# B2B_connectors.net
KiCad netlist of a schematic drawn in Altium Designer
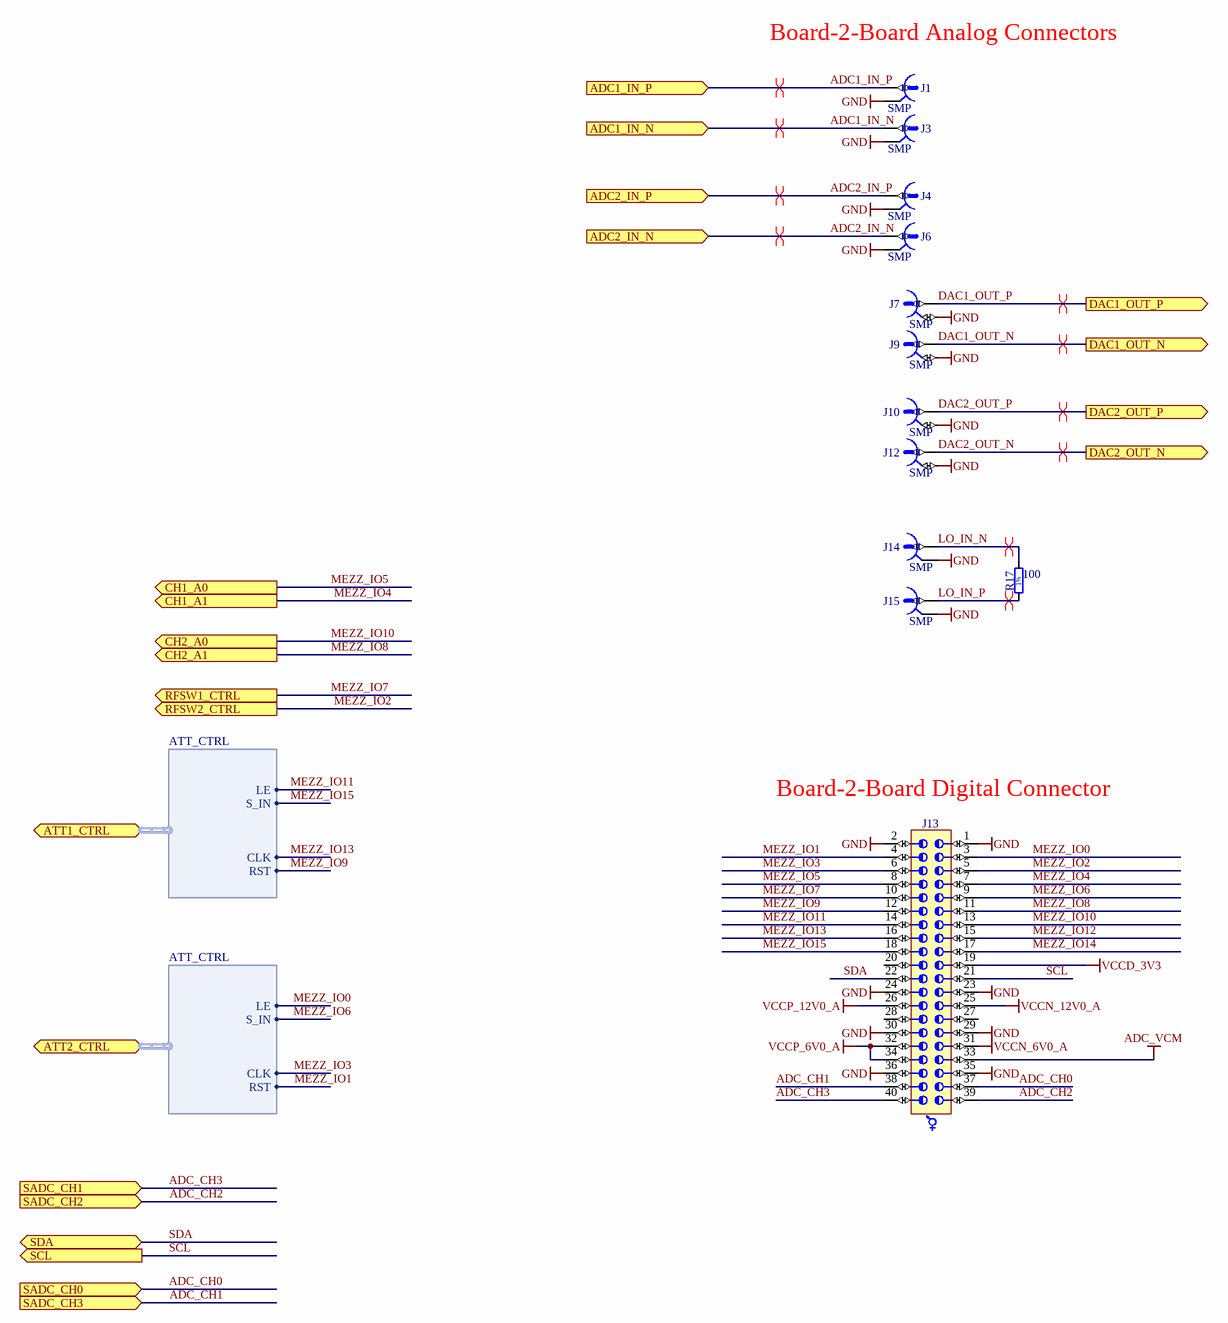
[diagram p0: B2B_connectors .SchDoc]

(export (version "E")
  (design (tool "Eeschema 10.0.6"))
  (components
    (comp (ref "J1")
      (value "SMP")
      (footprint "AMPHENOL_SMP-MSLD-PCT-10")
      (description "50 Ohms, SMP Surface/THT Mount Plug, Limited Detent")
      (fields
        (field (name "PART NUMBER") "AMPHENOL_SMP-MSLD-PCT-10")
        (field (name "MANUFACTURER") "AMPHENOL")
        (field (name "AUTHOR") "GK")
      )
      (libsource (lib "LIBRARY_SCH") (part "CON_SMP-MSLD-PCT-10"))
    )
    (comp (ref "J3")
      (value "SMP")
      (footprint "AMPHENOL_SMP-MSLD-PCT-10")
      (description "50 Ohms, SMP Surface/THT Mount Plug, Limited Detent")
      (fields
        (field (name "PART NUMBER") "AMPHENOL_SMP-MSLD-PCT-10")
        (field (name "MANUFACTURER") "AMPHENOL")
        (field (name "AUTHOR") "GK")
      )
      (libsource (lib "LIBRARY_SCH") (part "CON_SMP-MSLD-PCT-10"))
    )
    (comp (ref "J4")
      (value "SMP")
      (footprint "AMPHENOL_SMP-MSLD-PCT-10")
      (description "50 Ohms, SMP Surface/THT Mount Plug, Limited Detent")
      (fields
        (field (name "PART NUMBER") "AMPHENOL_SMP-MSLD-PCT-10")
        (field (name "MANUFACTURER") "AMPHENOL")
        (field (name "AUTHOR") "GK")
      )
      (libsource (lib "LIBRARY_SCH") (part "CON_SMP-MSLD-PCT-10"))
    )
    (comp (ref "J6")
      (value "SMP")
      (footprint "AMPHENOL_SMP-MSLD-PCT-10")
      (description "50 Ohms, SMP Surface/THT Mount Plug, Limited Detent")
      (fields
        (field (name "PART NUMBER") "AMPHENOL_SMP-MSLD-PCT-10")
        (field (name "MANUFACTURER") "AMPHENOL")
        (field (name "AUTHOR") "GK")
      )
      (libsource (lib "LIBRARY_SCH") (part "CON_SMP-MSLD-PCT-10"))
    )
    (comp (ref "J7")
      (value "SMP")
      (footprint "MOLEX_85305-0232")
      (fields
        (field (name "PART NUMBER") "MOLEX_85305-0232")
        (field (name "MANUFACTURER") "MOLEX")
        (field (name "MANUFACTURER PART NUMBER") "85305-0232")
        (field (name "AUTHOR") "CERN DEM JMW")
      )
      (libsource (lib "Connectors") (part "Coax_1Male_1Shield"))
    )
    (comp (ref "J9")
      (value "SMP")
      (footprint "MOLEX_85305-0232")
      (fields
        (field (name "PART NUMBER") "MOLEX_85305-0232")
        (field (name "MANUFACTURER") "MOLEX")
        (field (name "MANUFACTURER PART NUMBER") "85305-0232")
        (field (name "AUTHOR") "CERN DEM JMW")
      )
      (libsource (lib "Connectors") (part "Coax_1Male_1Shield"))
    )
    (comp (ref "J10")
      (value "SMP")
      (footprint "MOLEX_85305-0232")
      (fields
        (field (name "PART NUMBER") "MOLEX_85305-0232")
        (field (name "MANUFACTURER") "MOLEX")
        (field (name "MANUFACTURER PART NUMBER") "85305-0232")
        (field (name "AUTHOR") "CERN DEM JMW")
      )
      (libsource (lib "Connectors") (part "Coax_1Male_1Shield"))
    )
    (comp (ref "J12")
      (value "SMP")
      (footprint "MOLEX_85305-0232")
      (fields
        (field (name "PART NUMBER") "MOLEX_85305-0232")
        (field (name "MANUFACTURER") "MOLEX")
        (field (name "MANUFACTURER PART NUMBER") "85305-0232")
        (field (name "AUTHOR") "CERN DEM JMW")
      )
      (libsource (lib "Connectors") (part "Coax_1Male_1Shield"))
    )
    (comp (ref "J13")
      (value "~")
      (footprint "SAMTEC_LSS-120-02-L-DV-A")
      (fields
        (field (name "PART NUMBER") "SAMTEC_LSS-120-02-L-DV-A")
        (field (name "MANUFACTURER") "SAMTEC")
        (field (name "MANUFACTURER PART NUMBER") "LSS-120-02-L-DV-A")
        (field (name "AUTHOR") "CERN DEM JMW")
      )
      (libsource (lib "LIBRARY_SCH") (part "CON_SAMTEC_LSS-120-02-L-DV-A"))
    )
    (comp (ref "J14")
      (value "SMP")
      (footprint "AMPHENOL_SMP-MSLD-PCT-10")
      (description "50 Ohms, SMP Surface/THT Mount Plug, Limited Detent")
      (fields
        (field (name "PART NUMBER") "AMPHENOL_SMP-MSLD-PCT-10")
        (field (name "MANUFACTURER") "AMPHENOL")
        (field (name "AUTHOR") "GK")
      )
      (libsource (lib "") (part "CON_SMP-MSLD-PCT-10_1"))
    )
    (comp (ref "J15")
      (value "SMP")
      (footprint "AMPHENOL_SMP-MSLD-PCT-10")
      (description "50 Ohms, SMP Surface/THT Mount Plug, Limited Detent")
      (fields
        (field (name "PART NUMBER") "AMPHENOL_SMP-MSLD-PCT-10")
        (field (name "MANUFACTURER") "AMPHENOL")
        (field (name "AUTHOR") "GK")
      )
      (libsource (lib "") (part "CON_SMP-MSLD-PCT-10_1"))
    )
    (comp (ref "R17")
      (value "100")
      (footprint "RESC1005X40N")
      (description "Resistor - 1%")
      (fields
        (field (name "PART NUMBER") "R0402_100R_1%_0.0625W_100PPM")
        (field (name "POWER") "0.0625W")
        (field (name "AUTHOR") "CERN DEM JLC")
      )
      (libsource (lib "Resistors") (part "Resistor - 1%"))
    )
  )
  (nets
    (net (code "2") (name "/ADC1_IN_N") (class "Default")
      (node (ref "J3") (pin "1") (pinfunction "1_1") (pintype "bidirectional"))
    )
    (net (code "3") (name "/ADC1_IN_P") (class "Default")
      (node (ref "J1") (pin "1") (pinfunction "1_1") (pintype "bidirectional"))
    )
    (net (code "4") (name "/ADC2_IN_N") (class "Default")
      (node (ref "J6") (pin "1") (pinfunction "1_1") (pintype "bidirectional"))
    )
    (net (code "5") (name "/ADC2_IN_P") (class "Default")
      (node (ref "J4") (pin "1") (pinfunction "1_1") (pintype "bidirectional"))
    )
    (net (code "6") (name "/ADC_CH0") (class "Default")
      (node (ref "J13") (pin "37") (pinfunction "37_37") (pintype "bidirectional"))
    )
    (net (code "7") (name "/ADC_CH1") (class "Default")
      (node (ref "J13") (pin "38") (pinfunction "38_38") (pintype "bidirectional"))
    )
    (net (code "8") (name "/ADC_CH2") (class "Default")
      (node (ref "J13") (pin "39") (pinfunction "39_39") (pintype "bidirectional"))
    )
    (net (code "9") (name "/ADC_CH3") (class "Default")
      (node (ref "J13") (pin "40") (pinfunction "40_40") (pintype "bidirectional"))
    )
    (net (code "10") (name "/DAC1_OUT_N") (class "Default")
      (node (ref "J9") (pin "1") (pinfunction "1_1") (pintype "bidirectional"))
    )
    (net (code "11") (name "/DAC1_OUT_P") (class "Default")
      (node (ref "J7") (pin "1") (pinfunction "1_1") (pintype "bidirectional"))
    )
    (net (code "12") (name "/DAC2_OUT_N") (class "Default")
      (node (ref "J12") (pin "1") (pinfunction "1_1") (pintype "bidirectional"))
    )
    (net (code "13") (name "/DAC2_OUT_P") (class "Default")
      (node (ref "J10") (pin "1") (pinfunction "1_1") (pintype "bidirectional"))
    )
    (net (code "14") (name "/LO_IN_N") (class "Default")
      (node (ref "J14") (pin "1") (pinfunction "1_1") (pintype "bidirectional"))
      (node (ref "R17") (pin "2") (pinfunction "2_2") (pintype "passive"))
    )
    (net (code "15") (name "/LO_IN_P") (class "Default")
      (node (ref "J15") (pin "1") (pinfunction "1_1") (pintype "bidirectional"))
      (node (ref "R17") (pin "1") (pinfunction "1_1") (pintype "passive"))
    )
    (net (code "16") (name "/MEZZ_IO0") (class "Default")
      (node (ref "J13") (pin "3") (pinfunction "3_3") (pintype "bidirectional"))
    )
    (net (code "17") (name "/MEZZ_IO1") (class "Default")
      (node (ref "J13") (pin "4") (pinfunction "4_4") (pintype "bidirectional"))
    )
    (net (code "18") (name "/MEZZ_IO2") (class "Default")
      (node (ref "J13") (pin "5") (pinfunction "5_5") (pintype "bidirectional"))
    )
    (net (code "19") (name "/MEZZ_IO3") (class "Default")
      (node (ref "J13") (pin "6") (pinfunction "6_6") (pintype "bidirectional"))
    )
    (net (code "20") (name "/MEZZ_IO4") (class "Default")
      (node (ref "J13") (pin "7") (pinfunction "7_7") (pintype "bidirectional"))
    )
    (net (code "21") (name "/MEZZ_IO5") (class "Default")
      (node (ref "J13") (pin "8") (pinfunction "8_8") (pintype "bidirectional"))
    )
    (net (code "22") (name "/MEZZ_IO6") (class "Default")
      (node (ref "J13") (pin "9") (pinfunction "9_9") (pintype "bidirectional"))
    )
    (net (code "23") (name "/MEZZ_IO7") (class "Default")
      (node (ref "J13") (pin "10") (pinfunction "10_10") (pintype "bidirectional"))
    )
    (net (code "24") (name "/MEZZ_IO8") (class "Default")
      (node (ref "J13") (pin "11") (pinfunction "11_11") (pintype "bidirectional"))
    )
    (net (code "25") (name "/MEZZ_IO9") (class "Default")
      (node (ref "J13") (pin "12") (pinfunction "12_12") (pintype "bidirectional"))
    )
    (net (code "26") (name "/MEZZ_IO10") (class "Default")
      (node (ref "J13") (pin "13") (pinfunction "13_13") (pintype "bidirectional"))
    )
    (net (code "27") (name "/MEZZ_IO11") (class "Default")
      (node (ref "J13") (pin "14") (pinfunction "14_14") (pintype "bidirectional"))
    )
    (net (code "28") (name "/MEZZ_IO12") (class "Default")
      (node (ref "J13") (pin "15") (pinfunction "15_15") (pintype "bidirectional"))
    )
    (net (code "29") (name "/MEZZ_IO13") (class "Default")
      (node (ref "J13") (pin "16") (pinfunction "16_16") (pintype "bidirectional"))
    )
    (net (code "30") (name "/MEZZ_IO14") (class "Default")
      (node (ref "J13") (pin "17") (pinfunction "17_17") (pintype "bidirectional"))
    )
    (net (code "31") (name "/MEZZ_IO15") (class "Default")
      (node (ref "J13") (pin "18") (pinfunction "18_18") (pintype "bidirectional"))
    )
    (net (code "32") (name "/SCL") (class "Default")
      (node (ref "J13") (pin "21") (pinfunction "21_21") (pintype "bidirectional"))
    )
    (net (code "33") (name "/SDA") (class "Default")
      (node (ref "J13") (pin "22") (pinfunction "22_22") (pintype "bidirectional"))
    )
    (net (code "35") (name "ADC_VCM") (class "Default")
      (node (ref "J13") (pin "33") (pinfunction "33_33") (pintype "bidirectional"))
    )
    (net (code "36") (name "GND") (class "Default")
      (node (ref "J1") (pin "2") (pinfunction "2_2") (pintype "passive"))
      (node (ref "J10") (pin "2") (pinfunction "2_2") (pintype "bidirectional"))
      (node (ref "J12") (pin "2") (pinfunction "2_2") (pintype "bidirectional"))
      (node (ref "J13") (pin "1") (pinfunction "1_1") (pintype "bidirectional"))
      (node (ref "J13") (pin "2") (pinfunction "2_2") (pintype "bidirectional"))
      (node (ref "J13") (pin "23") (pinfunction "23_23") (pintype "bidirectional"))
      (node (ref "J13") (pin "24") (pinfunction "24_24") (pintype "bidirectional"))
      (node (ref "J13") (pin "29") (pinfunction "29_29") (pintype "bidirectional"))
      (node (ref "J13") (pin "30") (pinfunction "30_30") (pintype "bidirectional"))
      (node (ref "J13") (pin "35") (pinfunction "35_35") (pintype "bidirectional"))
      (node (ref "J13") (pin "36") (pinfunction "36_36") (pintype "bidirectional"))
      (node (ref "J14") (pin "2") (pinfunction "2_2") (pintype "passive"))
      (node (ref "J15") (pin "2") (pinfunction "2_2") (pintype "passive"))
      (node (ref "J3") (pin "2") (pinfunction "2_2") (pintype "passive"))
      (node (ref "J4") (pin "2") (pinfunction "2_2") (pintype "passive"))
      (node (ref "J6") (pin "2") (pinfunction "2_2") (pintype "passive"))
      (node (ref "J7") (pin "2") (pinfunction "2_2") (pintype "bidirectional"))
      (node (ref "J9") (pin "2") (pinfunction "2_2") (pintype "bidirectional"))
    )
    (net (code "37") (name "VCCD_3V3") (class "Default")
      (node (ref "J13") (pin "19") (pinfunction "19_19") (pintype "bidirectional"))
    )
    (net (code "38") (name "VCCN_6V0_A") (class "Default")
      (node (ref "J13") (pin "31") (pinfunction "31_31") (pintype "bidirectional"))
    )
    (net (code "39") (name "VCCN_12V0_A") (class "Default")
      (node (ref "J13") (pin "25") (pinfunction "25_25") (pintype "bidirectional"))
    )
    (net (code "40") (name "VCCP_6V0_A") (class "Default")
      (node (ref "J13") (pin "32") (pinfunction "32_32") (pintype "bidirectional"))
      (node (ref "J13") (pin "34") (pinfunction "34_34") (pintype "bidirectional"))
    )
    (net (code "41") (name "VCCP_12V0_A") (class "Default")
      (node (ref "J13") (pin "26") (pinfunction "26_26") (pintype "bidirectional"))
    )
    (net (code "42") (name "unconnected-(J13-Pad20)") (class "Default")
      (node (ref "J13") (pin "20") (pinfunction "20_20") (pintype "bidirectional"))
    )
    (net (code "43") (name "unconnected-(J13-Pad27)") (class "Default")
      (node (ref "J13") (pin "27") (pinfunction "27_27") (pintype "bidirectional"))
    )
    (net (code "44") (name "unconnected-(J13-Pad28)") (class "Default")
      (node (ref "J13") (pin "28") (pinfunction "28_28") (pintype "bidirectional"))
    )
  )
)
